# Ain.net
KiCad netlist of a schematic drawn in Altium Designer
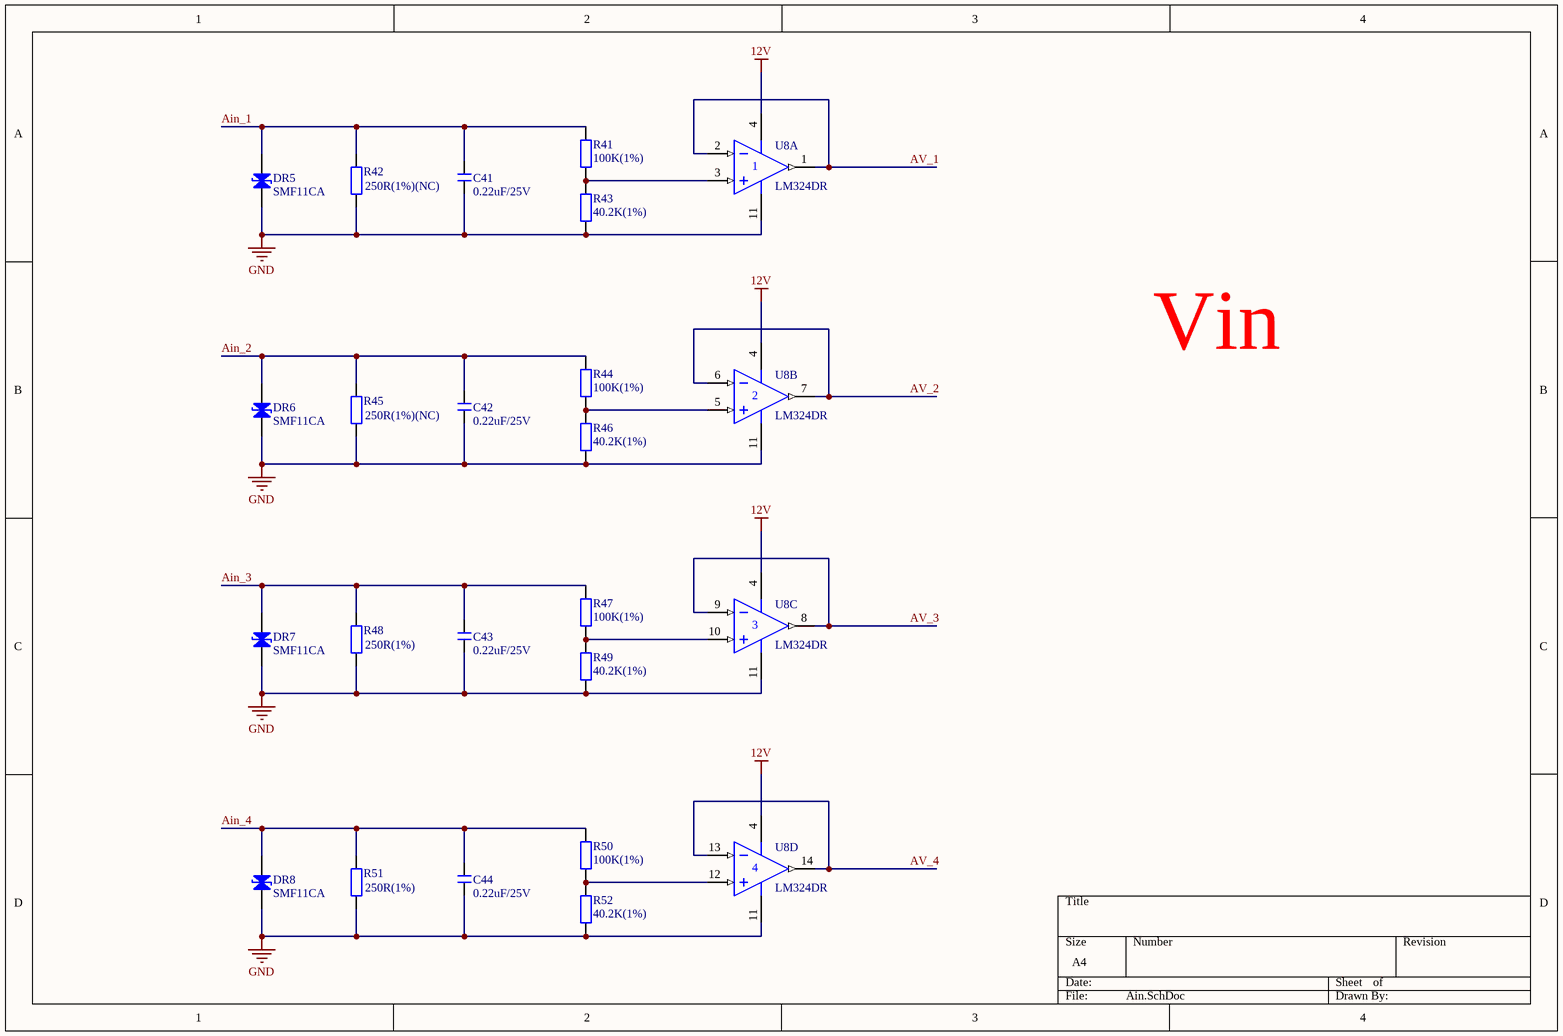
[diagram p0: Ain.SchDoc]

(export (version "E")
  (design (tool "Eeschema 10.0.6"))
  (components
    (comp (ref "C41")
      (value "0.22uF/25V")
      (footprint "C 0603_L")
      (description "无极性贴片电容")
      (fields (field (name "版权归属") "源创客"))
      (libsource (lib "电阻-电容-电感") (part "C"))
    )
    (comp (ref "C42")
      (value "0.22uF/25V")
      (footprint "C 0603_L")
      (description "无极性贴片电容")
      (fields (field (name "版权归属") "源创客"))
      (libsource (lib "电阻-电容-电感") (part "C"))
    )
    (comp (ref "C43")
      (value "0.22uF/25V")
      (footprint "C 0603_L")
      (description "无极性贴片电容")
      (fields (field (name "版权归属") "源创客"))
      (libsource (lib "电阻-电容-电感") (part "C"))
    )
    (comp (ref "C44")
      (value "0.22uF/25V")
      (footprint "C 0603_L")
      (description "无极性贴片电容")
      (fields (field (name "版权归属") "源创客"))
      (libsource (lib "电阻-电容-电感") (part "C"))
    )
    (comp (ref "DR5")
      (value "SMF11CA")
      (footprint "SOD-123F")
      (description "瞬态电压抑制二极管")
      (fields (field (name "版权归属") "源创客"))
      (libsource (lib "二极管-整流桥") (part "DR"))
    )
    (comp (ref "DR6")
      (value "SMF11CA")
      (footprint "SOD-123F")
      (description "瞬态电压抑制二极管")
      (fields (field (name "版权归属") "源创客"))
      (libsource (lib "二极管-整流桥") (part "DR"))
    )
    (comp (ref "DR7")
      (value "SMF11CA")
      (footprint "SOD-123F")
      (description "瞬态电压抑制二极管")
      (fields (field (name "版权归属") "源创客"))
      (libsource (lib "二极管-整流桥") (part "DR"))
    )
    (comp (ref "DR8")
      (value "SMF11CA")
      (footprint "SOD-123F")
      (description "瞬态电压抑制二极管")
      (fields (field (name "版权归属") "源创客"))
      (libsource (lib "二极管-整流桥") (part "DR"))
    )
    (comp (ref "R41")
      (value "100K(1%)")
      (footprint "R 0603_L")
      (description "贴片电阻")
      (fields (field (name "版权归属") "源创客"))
      (libsource (lib "电阻-电容-电感") (part "R"))
    )
    (comp (ref "R42")
      (value "250R(1%)(NC)")
      (footprint "R 0603_L")
      (description "贴片电阻")
      (fields (field (name "版权归属") "源创客"))
      (libsource (lib "电阻-电容-电感") (part "R"))
    )
    (comp (ref "R43")
      (value "40.2K(1%)")
      (footprint "R 0603_L")
      (description "贴片电阻")
      (fields (field (name "版权归属") "源创客"))
      (libsource (lib "电阻-电容-电感") (part "R"))
    )
    (comp (ref "R44")
      (value "100K(1%)")
      (footprint "R 0603_L")
      (description "贴片电阻")
      (fields (field (name "版权归属") "源创客"))
      (libsource (lib "电阻-电容-电感") (part "R"))
    )
    (comp (ref "R45")
      (value "250R(1%)(NC)")
      (footprint "R 0603_L")
      (description "贴片电阻")
      (fields (field (name "版权归属") "源创客"))
      (libsource (lib "电阻-电容-电感") (part "R"))
    )
    (comp (ref "R46")
      (value "40.2K(1%)")
      (footprint "R 0603_L")
      (description "贴片电阻")
      (fields (field (name "版权归属") "源创客"))
      (libsource (lib "电阻-电容-电感") (part "R"))
    )
    (comp (ref "R47")
      (value "100K(1%)")
      (footprint "R 0603_L")
      (description "贴片电阻")
      (fields (field (name "版权归属") "源创客"))
      (libsource (lib "电阻-电容-电感") (part "R"))
    )
    (comp (ref "R48")
      (value "250R(1%)")
      (footprint "R 0603_L")
      (description "贴片电阻")
      (fields (field (name "版权归属") "源创客"))
      (libsource (lib "电阻-电容-电感") (part "R"))
    )
    (comp (ref "R49")
      (value "40.2K(1%)")
      (footprint "R 0603_L")
      (description "贴片电阻")
      (fields (field (name "版权归属") "源创客"))
      (libsource (lib "电阻-电容-电感") (part "R"))
    )
    (comp (ref "R50")
      (value "100K(1%)")
      (footprint "R 0603_L")
      (description "贴片电阻")
      (fields (field (name "版权归属") "源创客"))
      (libsource (lib "电阻-电容-电感") (part "R"))
    )
    (comp (ref "R51")
      (value "250R(1%)")
      (footprint "R 0603_L")
      (description "贴片电阻")
      (fields (field (name "版权归属") "源创客"))
      (libsource (lib "电阻-电容-电感") (part "R"))
    )
    (comp (ref "R52")
      (value "40.2K(1%)")
      (footprint "R 0603_L")
      (description "贴片电阻")
      (fields (field (name "版权归属") "源创客"))
      (libsource (lib "电阻-电容-电感") (part "R"))
    )
    (comp (ref "U8")
      (value "LM324DR")
      (footprint "D014_N")
      (description "Quadruple Operational Amplifier")
      (fields (field (name "PUBLISHER") "Altium Limited"))
      (libsource (lib "MICB") (part "LM324DR"))
    )
  )
  (nets
    (net (code "1") (name "/AV_1") (class "Default")
      (node (ref "U8") (pin "1") (pinfunction "OUT_1") (pintype "output"))
      (node (ref "U8") (pin "2") (pinfunction "IN-_2") (pintype "input"))
    )
    (net (code "2") (name "/AV_2") (class "Default")
      (node (ref "U8") (pin "6") (pinfunction "IN-_6") (pintype "input"))
      (node (ref "U8") (pin "7") (pinfunction "OUT_7") (pintype "output"))
    )
    (net (code "3") (name "/AV_3") (class "Default")
      (node (ref "U8") (pin "8") (pinfunction "OUT_8") (pintype "output"))
      (node (ref "U8") (pin "9") (pinfunction "IN-_9") (pintype "input"))
    )
    (net (code "4") (name "/AV_4") (class "Default")
      (node (ref "U8") (pin "13") (pinfunction "IN-_13") (pintype "input"))
      (node (ref "U8") (pin "14") (pinfunction "OUT_14") (pintype "output"))
    )
    (net (code "5") (name "/Ain_1") (class "Default")
      (node (ref "C41") (pin "2") (pinfunction "2_2") (pintype "passive"))
      (node (ref "DR5") (pin "1") (pinfunction "A_1") (pintype "passive"))
      (node (ref "R41") (pin "2") (pinfunction "2_2") (pintype "passive"))
      (node (ref "R42") (pin "2") (pinfunction "2_2") (pintype "passive"))
    )
    (net (code "6") (name "/Ain_2") (class "Default")
      (node (ref "C42") (pin "2") (pinfunction "2_2") (pintype "passive"))
      (node (ref "DR6") (pin "1") (pinfunction "A_1") (pintype "passive"))
      (node (ref "R44") (pin "2") (pinfunction "2_2") (pintype "passive"))
      (node (ref "R45") (pin "2") (pinfunction "2_2") (pintype "passive"))
    )
    (net (code "7") (name "/Ain_3") (class "Default")
      (node (ref "C43") (pin "2") (pinfunction "2_2") (pintype "passive"))
      (node (ref "DR7") (pin "1") (pinfunction "A_1") (pintype "passive"))
      (node (ref "R47") (pin "2") (pinfunction "2_2") (pintype "passive"))
      (node (ref "R48") (pin "2") (pinfunction "2_2") (pintype "passive"))
    )
    (net (code "8") (name "/Ain_4") (class "Default")
      (node (ref "C44") (pin "2") (pinfunction "2_2") (pintype "passive"))
      (node (ref "DR8") (pin "1") (pinfunction "A_1") (pintype "passive"))
      (node (ref "R50") (pin "2") (pinfunction "2_2") (pintype "passive"))
      (node (ref "R51") (pin "2") (pinfunction "2_2") (pintype "passive"))
    )
    (net (code "9") (name "12V") (class "Default")
      (node (ref "U8") (pin "4") (pinfunction "V+_4") (pintype "power_in"))
    )
    (net (code "10") (name "GND") (class "Default")
      (node (ref "C41") (pin "1") (pinfunction "1_1") (pintype "passive"))
      (node (ref "C42") (pin "1") (pinfunction "1_1") (pintype "passive"))
      (node (ref "C43") (pin "1") (pinfunction "1_1") (pintype "passive"))
      (node (ref "C44") (pin "1") (pinfunction "1_1") (pintype "passive"))
      (node (ref "DR5") (pin "2") (pinfunction "K_2") (pintype "passive"))
      (node (ref "DR6") (pin "2") (pinfunction "K_2") (pintype "passive"))
      (node (ref "DR7") (pin "2") (pinfunction "K_2") (pintype "passive"))
      (node (ref "DR8") (pin "2") (pinfunction "K_2") (pintype "passive"))
      (node (ref "R42") (pin "1") (pinfunction "1_1") (pintype "passive"))
      (node (ref "R43") (pin "1") (pinfunction "1_1") (pintype "passive"))
      (node (ref "R45") (pin "1") (pinfunction "1_1") (pintype "passive"))
      (node (ref "R46") (pin "1") (pinfunction "1_1") (pintype "passive"))
      (node (ref "R48") (pin "1") (pinfunction "1_1") (pintype "passive"))
      (node (ref "R49") (pin "1") (pinfunction "1_1") (pintype "passive"))
      (node (ref "R51") (pin "1") (pinfunction "1_1") (pintype "passive"))
      (node (ref "R52") (pin "1") (pinfunction "1_1") (pintype "passive"))
      (node (ref "U8") (pin "11") (pinfunction "V-_11") (pintype "power_in"))
    )
    (net (code "11") (name "Net-(U8A-IN+)") (class "Default")
      (node (ref "R41") (pin "1") (pinfunction "1_1") (pintype "passive"))
      (node (ref "R43") (pin "2") (pinfunction "2_2") (pintype "passive"))
      (node (ref "U8") (pin "3") (pinfunction "IN+_3") (pintype "input"))
    )
    (net (code "12") (name "Net-(U8B-IN+)") (class "Default")
      (node (ref "R44") (pin "1") (pinfunction "1_1") (pintype "passive"))
      (node (ref "R46") (pin "2") (pinfunction "2_2") (pintype "passive"))
      (node (ref "U8") (pin "5") (pinfunction "IN+_5") (pintype "input"))
    )
    (net (code "13") (name "Net-(U8C-IN+)") (class "Default")
      (node (ref "R47") (pin "1") (pinfunction "1_1") (pintype "passive"))
      (node (ref "R49") (pin "2") (pinfunction "2_2") (pintype "passive"))
      (node (ref "U8") (pin "10") (pinfunction "IN+_10") (pintype "input"))
    )
    (net (code "14") (name "Net-(U8D-IN+)") (class "Default")
      (node (ref "R50") (pin "1") (pinfunction "1_1") (pintype "passive"))
      (node (ref "R52") (pin "2") (pinfunction "2_2") (pintype "passive"))
      (node (ref "U8") (pin "12") (pinfunction "IN+_12") (pintype "input"))
    )
  )
)
